# Lock-In.net
KiCad netlist of a schematic drawn in EAGLE
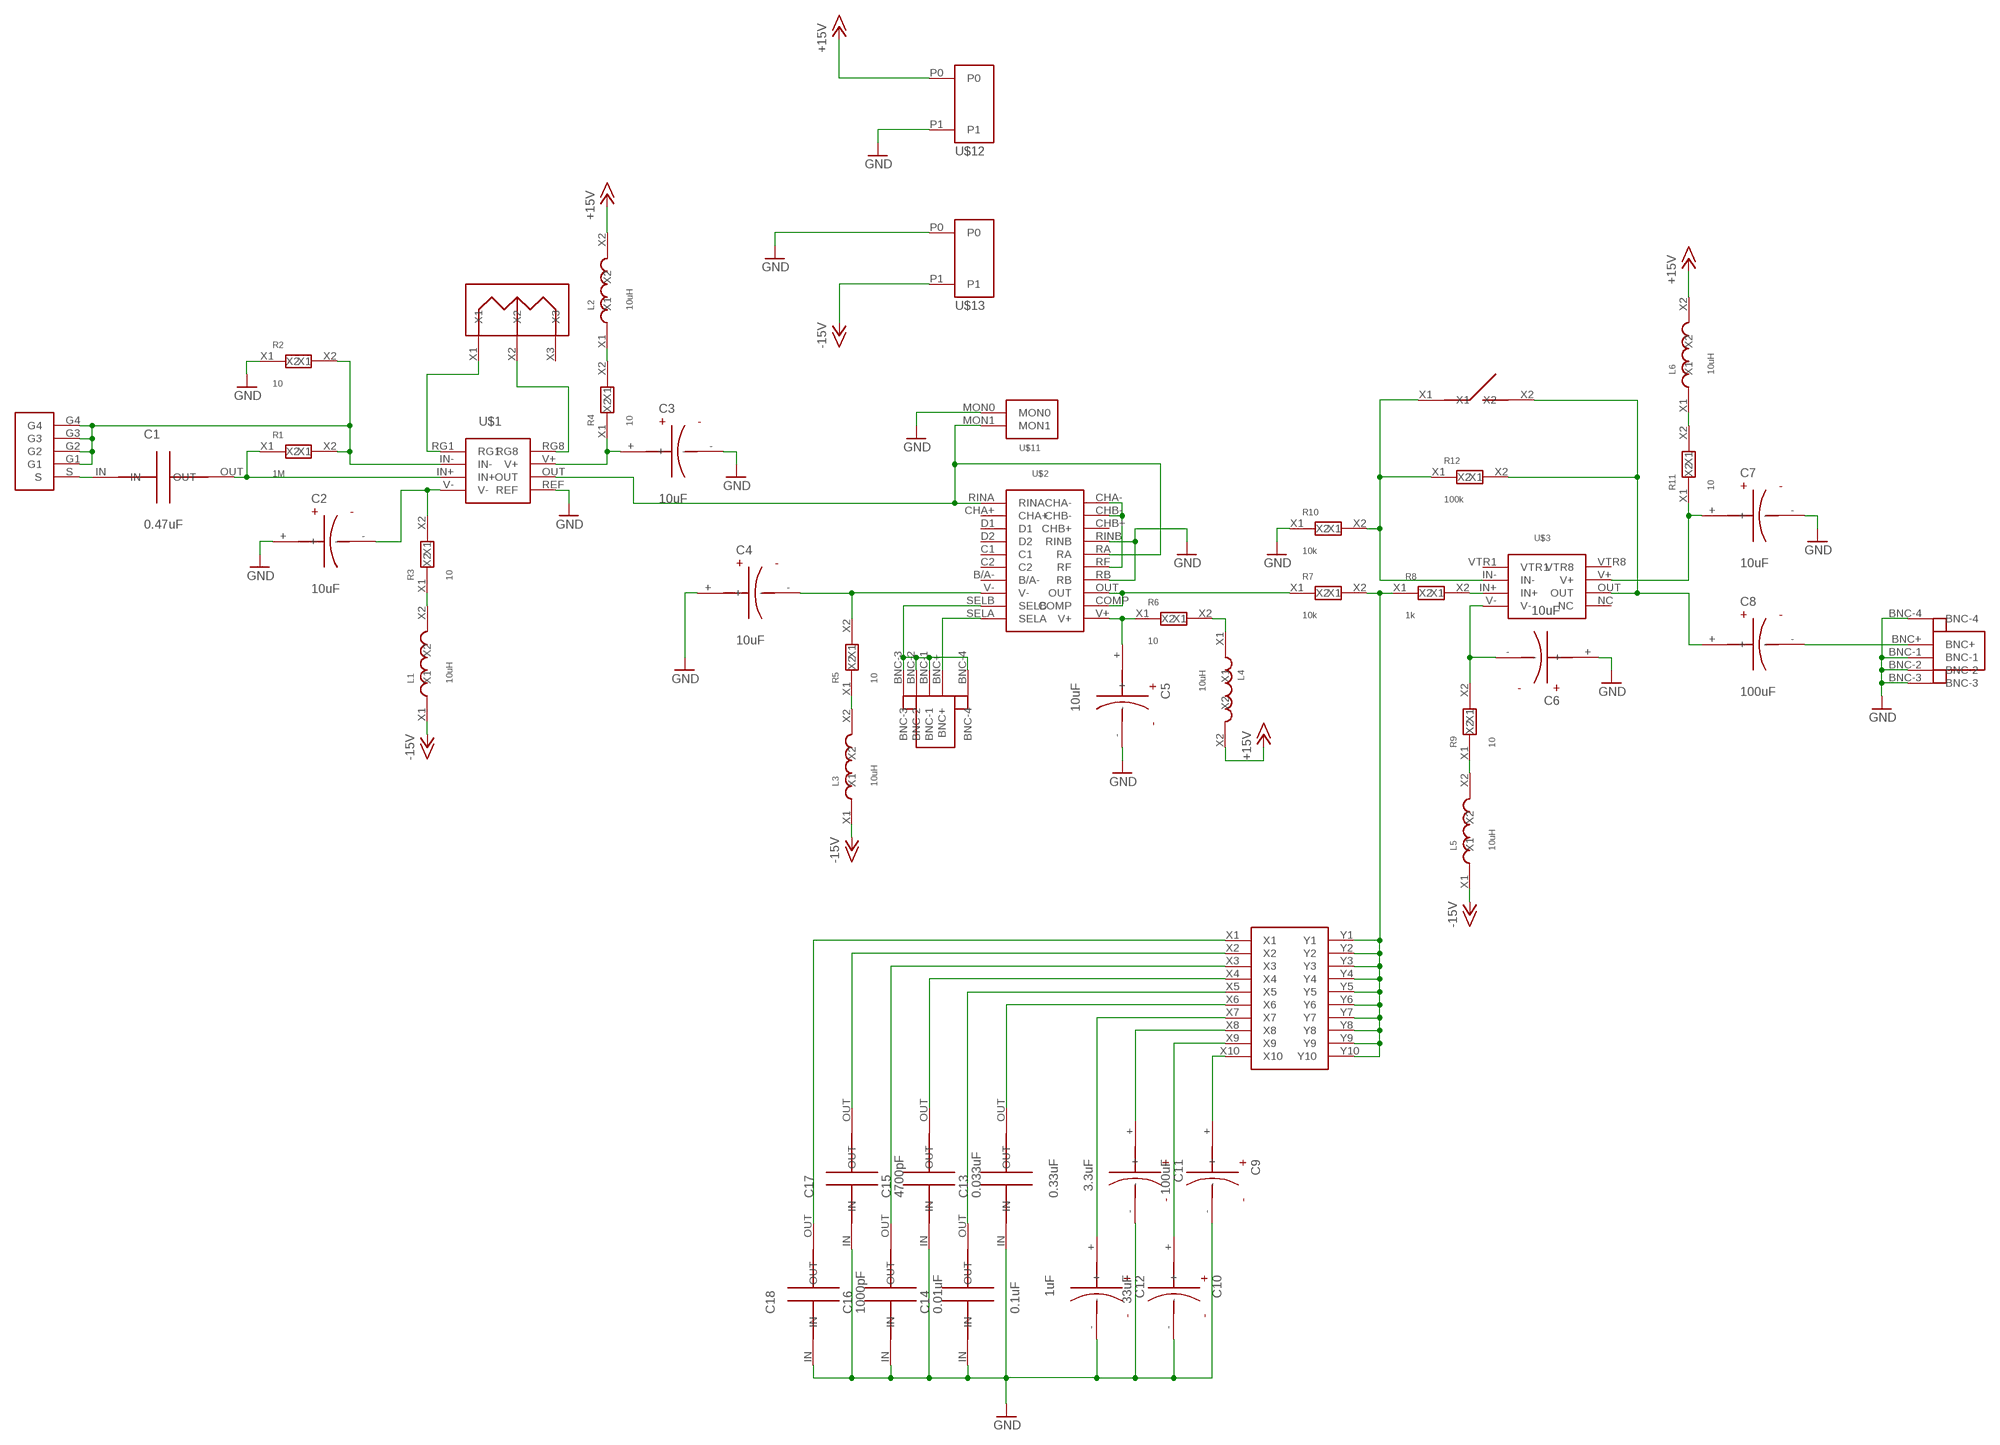
[diagram p0: schematic, sheet 1]

(export (version "E")
  (design (tool "Eeschema 10.0.6"))
  (components
    (comp (ref "C1")
      (value "0.47uF")
      (footprint "eagle-import:C_CER_5MM")
      (libsource (lib "eagle-import") (part "C_CER_5MM"))
    )
    (comp (ref "C2")
      (value "10uF")
      (footprint "eagle-import:C_ELT_2MM")
      (libsource (lib "eagle-import") (part "C_ELT_2MM"))
    )
    (comp (ref "C3")
      (value "10uF")
      (footprint "eagle-import:C_ELT_2MM")
      (libsource (lib "eagle-import") (part "C_ELT_2MM"))
    )
    (comp (ref "C4")
      (value "10uF")
      (footprint "eagle-import:C_ELT_2MM")
      (libsource (lib "eagle-import") (part "C_ELT_2MM"))
    )
    (comp (ref "C5")
      (value "10uF")
      (footprint "eagle-import:C_ELT_2MM")
      (libsource (lib "eagle-import") (part "C_ELT_2MM"))
    )
    (comp (ref "C6")
      (value "10uF")
      (footprint "eagle-import:C_ELT_2MM")
      (libsource (lib "eagle-import") (part "C_ELT_2MM"))
    )
    (comp (ref "C7")
      (value "10uF")
      (footprint "eagle-import:C_ELT_2MM")
      (libsource (lib "eagle-import") (part "C_ELT_2MM"))
    )
    (comp (ref "C8")
      (value "100uF")
      (footprint "eagle-import:C_ELT_2MM")
      (libsource (lib "eagle-import") (part "C_ELT_2MM"))
    )
    (comp (ref "C9")
      (value "100uF")
      (footprint "eagle-import:C_ELT_2MM")
      (libsource (lib "eagle-import") (part "C_ELT_2MM"))
    )
    (comp (ref "C10")
      (value "33uF")
      (footprint "eagle-import:C_ELT_2MM")
      (libsource (lib "eagle-import") (part "C_ELT_2MM"))
    )
    (comp (ref "C11")
      (value "3.3uF")
      (footprint "eagle-import:C_ELT_2MM")
      (libsource (lib "eagle-import") (part "C_ELT_2MM"))
    )
    (comp (ref "C12")
      (value "1uF")
      (footprint "eagle-import:C_ELT_2MM")
      (libsource (lib "eagle-import") (part "C_ELT_2MM"))
    )
    (comp (ref "C13")
      (value "0.33uF")
      (footprint "eagle-import:C_CER_5MM")
      (libsource (lib "eagle-import") (part "C_CER_5MM"))
    )
    (comp (ref "C14")
      (value "0.1uF")
      (footprint "eagle-import:C_CER_5MM")
      (libsource (lib "eagle-import") (part "C_CER_5MM"))
    )
    (comp (ref "C15")
      (value "0.033uF")
      (footprint "eagle-import:C_CER_5MM")
      (libsource (lib "eagle-import") (part "C_CER_5MM"))
    )
    (comp (ref "C16")
      (value "0.01uF")
      (footprint "eagle-import:C_CER_5MM")
      (libsource (lib "eagle-import") (part "C_CER_5MM"))
    )
    (comp (ref "C17")
      (value "4700pF")
      (footprint "eagle-import:C_CER_5MM")
      (libsource (lib "eagle-import") (part "C_CER_5MM"))
    )
    (comp (ref "C18")
      (value "1000pF")
      (footprint "eagle-import:C_CER_5MM")
      (libsource (lib "eagle-import") (part "C_CER_5MM"))
    )
    (comp (ref "L1")
      (value "10uH")
      (footprint "eagle-import:L_10X3")
      (libsource (lib "eagle-import") (part "L_10X3"))
    )
    (comp (ref "L2")
      (value "10uH")
      (footprint "eagle-import:L_10X3")
      (libsource (lib "eagle-import") (part "L_10X3"))
    )
    (comp (ref "L3")
      (value "10uH")
      (footprint "eagle-import:L_10X3")
      (libsource (lib "eagle-import") (part "L_10X3"))
    )
    (comp (ref "L4")
      (value "10uH")
      (footprint "eagle-import:L_10X3")
      (libsource (lib "eagle-import") (part "L_10X3"))
    )
    (comp (ref "L5")
      (value "10uH")
      (footprint "eagle-import:L_10X3")
      (libsource (lib "eagle-import") (part "L_10X3"))
    )
    (comp (ref "L6")
      (value "10uH")
      (footprint "eagle-import:L_10X3")
      (libsource (lib "eagle-import") (part "L_10X3"))
    )
    (comp (ref "R1")
      (value "1M")
      (footprint "eagle-import:R_6X2")
      (libsource (lib "eagle-import") (part "R_6X2"))
    )
    (comp (ref "R2")
      (value "10")
      (footprint "eagle-import:R_6X2")
      (libsource (lib "eagle-import") (part "R_6X2"))
    )
    (comp (ref "R3")
      (value "10")
      (footprint "eagle-import:R_6X2")
      (libsource (lib "eagle-import") (part "R_6X2"))
    )
    (comp (ref "R4")
      (value "10")
      (footprint "eagle-import:R_6X2")
      (libsource (lib "eagle-import") (part "R_6X2"))
    )
    (comp (ref "R5")
      (value "10")
      (footprint "eagle-import:R_6X2")
      (libsource (lib "eagle-import") (part "R_6X2"))
    )
    (comp (ref "R6")
      (value "10")
      (footprint "eagle-import:R_6X2")
      (libsource (lib "eagle-import") (part "R_6X2"))
    )
    (comp (ref "R7")
      (value "10k")
      (footprint "eagle-import:R_6X2")
      (libsource (lib "eagle-import") (part "R_6X2"))
    )
    (comp (ref "R8")
      (value "1k")
      (footprint "eagle-import:R_6X2")
      (libsource (lib "eagle-import") (part "R_6X2"))
    )
    (comp (ref "R9")
      (value "10")
      (footprint "eagle-import:R_6X2")
      (libsource (lib "eagle-import") (part "R_6X2"))
    )
    (comp (ref "R10")
      (value "10k")
      (footprint "eagle-import:R_6X2")
      (libsource (lib "eagle-import") (part "R_6X2"))
    )
    (comp (ref "R11")
      (value "10")
      (footprint "eagle-import:R_6X2")
      (libsource (lib "eagle-import") (part "R_6X2"))
    )
    (comp (ref "R12")
      (value "100k")
      (footprint "eagle-import:R_6X2")
      (libsource (lib "eagle-import") (part "R_6X2"))
    )
    (comp (ref "U$1")
      (value "AD620N")
      (footprint "eagle-import:AD620N")
      (libsource (lib "eagle-import") (part "AD620N"))
    )
    (comp (ref "U$2")
      (value "AD630")
      (footprint "eagle-import:AD630")
      (libsource (lib "eagle-import") (part "AD630"))
    )
    (comp (ref "U$3")
      (value "OP27")
      (footprint "eagle-import:OP27")
      (libsource (lib "eagle-import") (part "OP27"))
    )
    (comp (ref "U$4")
      (value "BNC")
      (footprint "eagle-import:BNC")
      (libsource (lib "eagle-import") (part "BNC"))
    )
    (comp (ref "U$5")
      (value "BNC")
      (footprint "eagle-import:BNC")
      (libsource (lib "eagle-import") (part "BNC"))
    )
    (comp (ref "U$6")
      (value "DIP10")
      (footprint "eagle-import:DIP10")
      (libsource (lib "eagle-import") (part "DIP10"))
    )
    (comp (ref "U$7")
      (value "R_VAR_10K")
      (footprint "eagle-import:R_VAR_10K")
      (libsource (lib "eagle-import") (part "R_VAR_10K"))
    )
    (comp (ref "U$8")
      (value "SMA_AN")
      (footprint "eagle-import:SMA_AN")
      (libsource (lib "eagle-import") (part "SMA_AN"))
    )
    (comp (ref "U$9")
      (value "DIP_1")
      (footprint "eagle-import:DIP_1")
      (libsource (lib "eagle-import") (part "DIP_1"))
    )
    (comp (ref "U$11")
      (value "MON2PIN")
      (footprint "eagle-import:MON2PIN")
      (libsource (lib "eagle-import") (part "MON2PIN"))
    )
    (comp (ref "U$12")
      (value "RAIL_2")
      (footprint "eagle-import:RAIL_2")
      (libsource (lib "eagle-import") (part "RAIL_2"))
    )
    (comp (ref "U$13")
      (value "RAIL_2")
      (footprint "eagle-import:RAIL_2")
      (libsource (lib "eagle-import") (part "RAIL_2"))
    )
  )
  (nets
    (net (code "1") (name "+15V") (class "Default")
      (node (ref "L2") (pin "X2") (pinfunction "X2_X2") (pintype "bidirectional"))
      (node (ref "L4") (pin "X2") (pinfunction "X2_X2") (pintype "bidirectional"))
      (node (ref "L6") (pin "X2") (pinfunction "X2_X2") (pintype "bidirectional"))
      (node (ref "U$12") (pin "P0") (pinfunction "P0_P0") (pintype "bidirectional"))
    )
    (net (code "2") (name "-15V") (class "Default")
      (node (ref "L1") (pin "X1") (pinfunction "X1_X1") (pintype "bidirectional"))
      (node (ref "L3") (pin "X1") (pinfunction "X1_X1") (pintype "bidirectional"))
      (node (ref "L5") (pin "X1") (pinfunction "X1_X1") (pintype "bidirectional"))
      (node (ref "U$13") (pin "P1") (pinfunction "P1_P1") (pintype "bidirectional"))
    )
    (net (code "3") (name "GND") (class "Default")
      (node (ref "C10") (pin "-") (pinfunction "-_-") (pintype "bidirectional"))
      (node (ref "C11") (pin "-") (pinfunction "-_-") (pintype "bidirectional"))
      (node (ref "C12") (pin "-") (pinfunction "-_-") (pintype "bidirectional"))
      (node (ref "C13") (pin "IN") (pinfunction "IN_IN") (pintype "bidirectional"))
      (node (ref "C14") (pin "IN") (pinfunction "IN_IN") (pintype "bidirectional"))
      (node (ref "C15") (pin "IN") (pinfunction "IN_IN") (pintype "bidirectional"))
      (node (ref "C16") (pin "IN") (pinfunction "IN_IN") (pintype "bidirectional"))
      (node (ref "C17") (pin "IN") (pinfunction "IN_IN") (pintype "bidirectional"))
      (node (ref "C18") (pin "IN") (pinfunction "IN_IN") (pintype "bidirectional"))
      (node (ref "C2") (pin "+") (pinfunction "+_+") (pintype "bidirectional"))
      (node (ref "C3") (pin "-") (pinfunction "-_-") (pintype "bidirectional"))
      (node (ref "C4") (pin "+") (pinfunction "+_+") (pintype "bidirectional"))
      (node (ref "C5") (pin "-") (pinfunction "-_-") (pintype "bidirectional"))
      (node (ref "C6") (pin "+") (pinfunction "+_+") (pintype "bidirectional"))
      (node (ref "C7") (pin "-") (pinfunction "-_-") (pintype "bidirectional"))
      (node (ref "C9") (pin "-") (pinfunction "-_-") (pintype "bidirectional"))
      (node (ref "R10") (pin "X1") (pinfunction "X1_X1") (pintype "bidirectional"))
      (node (ref "R2") (pin "X1") (pinfunction "X1_X1") (pintype "bidirectional"))
      (node (ref "U$1") (pin "REF") (pinfunction "REF_REF") (pintype "bidirectional"))
      (node (ref "U$11") (pin "MON0") (pinfunction "MON0_MON0") (pintype "bidirectional"))
      (node (ref "U$12") (pin "P1") (pinfunction "P1_P1") (pintype "bidirectional"))
      (node (ref "U$13") (pin "P0") (pinfunction "P0_P0") (pintype "bidirectional"))
      (node (ref "U$2") (pin "RB") (pinfunction "RB_RB") (pintype "bidirectional"))
      (node (ref "U$2") (pin "RINB") (pinfunction "RINB_RINB") (pintype "bidirectional"))
      (node (ref "U$5") (pin "BNC-1") (pinfunction "BNC-1_BNC-1") (pintype "bidirectional"))
      (node (ref "U$5") (pin "BNC-2") (pinfunction "BNC-2_BNC-2") (pintype "bidirectional"))
      (node (ref "U$5") (pin "BNC-3") (pinfunction "BNC-3_BNC-3") (pintype "bidirectional"))
      (node (ref "U$5") (pin "BNC-4") (pinfunction "BNC-4_BNC-4") (pintype "bidirectional"))
    )
    (net (code "4") (name "Net-(C1-PadIN)") (class "Default")
      (node (ref "C1") (pin "IN") (pinfunction "IN_IN") (pintype "bidirectional"))
      (node (ref "U$8") (pin "S") (pinfunction "S_S") (pintype "bidirectional"))
    )
    (net (code "5") (name "Net-(C1-PadOUT)") (class "Default")
      (node (ref "C1") (pin "OUT") (pinfunction "OUT_OUT") (pintype "bidirectional"))
      (node (ref "R1") (pin "X1") (pinfunction "X1_X1") (pintype "bidirectional"))
      (node (ref "U$1") (pin "IN+") (pinfunction "IN+_IN+") (pintype "bidirectional"))
    )
    (net (code "6") (name "Net-(C2-Pad-)") (class "Default")
      (node (ref "C2") (pin "-") (pinfunction "-_-") (pintype "bidirectional"))
      (node (ref "R3") (pin "X2") (pinfunction "X2_X2") (pintype "bidirectional"))
      (node (ref "U$1") (pin "V-") (pinfunction "V-_V-") (pintype "bidirectional"))
    )
    (net (code "7") (name "Net-(C3-Pad+)") (class "Default")
      (node (ref "C3") (pin "+") (pinfunction "+_+") (pintype "bidirectional"))
      (node (ref "R4") (pin "X1") (pinfunction "X1_X1") (pintype "bidirectional"))
      (node (ref "U$1") (pin "V+") (pinfunction "V+_V+") (pintype "bidirectional"))
    )
    (net (code "8") (name "Net-(C4-Pad-)") (class "Default")
      (node (ref "C4") (pin "-") (pinfunction "-_-") (pintype "bidirectional"))
      (node (ref "R5") (pin "X2") (pinfunction "X2_X2") (pintype "bidirectional"))
      (node (ref "U$2") (pin "V-") (pinfunction "V-_V-") (pintype "bidirectional"))
    )
    (net (code "9") (name "Net-(C5-Pad+)") (class "Default")
      (node (ref "C5") (pin "+") (pinfunction "+_+") (pintype "bidirectional"))
      (node (ref "R6") (pin "X1") (pinfunction "X1_X1") (pintype "bidirectional"))
      (node (ref "U$2") (pin "V+") (pinfunction "V+_V+") (pintype "bidirectional"))
    )
    (net (code "10") (name "Net-(C6-Pad-)") (class "Default")
      (node (ref "C6") (pin "-") (pinfunction "-_-") (pintype "bidirectional"))
      (node (ref "R9") (pin "X2") (pinfunction "X2_X2") (pintype "bidirectional"))
      (node (ref "U$3") (pin "V-") (pinfunction "V-_V-") (pintype "bidirectional"))
    )
    (net (code "11") (name "Net-(C7-Pad+)") (class "Default")
      (node (ref "C7") (pin "+") (pinfunction "+_+") (pintype "bidirectional"))
      (node (ref "R11") (pin "X1") (pinfunction "X1_X1") (pintype "bidirectional"))
      (node (ref "U$3") (pin "V+") (pinfunction "V+_V+") (pintype "bidirectional"))
    )
    (net (code "12") (name "Net-(C8-Pad+)") (class "Default")
      (node (ref "C8") (pin "+") (pinfunction "+_+") (pintype "bidirectional"))
      (node (ref "R12") (pin "X2") (pinfunction "X2_X2") (pintype "bidirectional"))
      (node (ref "U$3") (pin "OUT") (pinfunction "OUT_OUT") (pintype "bidirectional"))
      (node (ref "U$9") (pin "X2") (pinfunction "X2_X2") (pintype "bidirectional"))
    )
    (net (code "13") (name "Net-(C8-Pad-)") (class "Default")
      (node (ref "C8") (pin "-") (pinfunction "-_-") (pintype "bidirectional"))
      (node (ref "U$5") (pin "BNC+") (pinfunction "BNC+_BNC+") (pintype "bidirectional"))
    )
    (net (code "14") (name "Net-(C9-Pad+)") (class "Default")
      (node (ref "C9") (pin "+") (pinfunction "+_+") (pintype "bidirectional"))
      (node (ref "U$6") (pin "X10") (pinfunction "X10_X10") (pintype "bidirectional"))
    )
    (net (code "15") (name "Net-(C10-Pad+)") (class "Default")
      (node (ref "C10") (pin "+") (pinfunction "+_+") (pintype "bidirectional"))
      (node (ref "U$6") (pin "X9") (pinfunction "X9_X9") (pintype "bidirectional"))
    )
    (net (code "16") (name "Net-(C11-Pad+)") (class "Default")
      (node (ref "C11") (pin "+") (pinfunction "+_+") (pintype "bidirectional"))
      (node (ref "U$6") (pin "X8") (pinfunction "X8_X8") (pintype "bidirectional"))
    )
    (net (code "17") (name "Net-(C12-Pad+)") (class "Default")
      (node (ref "C12") (pin "+") (pinfunction "+_+") (pintype "bidirectional"))
      (node (ref "U$6") (pin "X7") (pinfunction "X7_X7") (pintype "bidirectional"))
    )
    (net (code "18") (name "Net-(C13-PadOUT)") (class "Default")
      (node (ref "C13") (pin "OUT") (pinfunction "OUT_OUT") (pintype "bidirectional"))
      (node (ref "U$6") (pin "X6") (pinfunction "X6_X6") (pintype "bidirectional"))
    )
    (net (code "19") (name "Net-(C14-PadOUT)") (class "Default")
      (node (ref "C14") (pin "OUT") (pinfunction "OUT_OUT") (pintype "bidirectional"))
      (node (ref "U$6") (pin "X5") (pinfunction "X5_X5") (pintype "bidirectional"))
    )
    (net (code "20") (name "Net-(C15-PadOUT)") (class "Default")
      (node (ref "C15") (pin "OUT") (pinfunction "OUT_OUT") (pintype "bidirectional"))
      (node (ref "U$6") (pin "X4") (pinfunction "X4_X4") (pintype "bidirectional"))
    )
    (net (code "21") (name "Net-(C16-PadOUT)") (class "Default")
      (node (ref "C16") (pin "OUT") (pinfunction "OUT_OUT") (pintype "bidirectional"))
      (node (ref "U$6") (pin "X3") (pinfunction "X3_X3") (pintype "bidirectional"))
    )
    (net (code "22") (name "Net-(C17-PadOUT)") (class "Default")
      (node (ref "C17") (pin "OUT") (pinfunction "OUT_OUT") (pintype "bidirectional"))
      (node (ref "U$6") (pin "X2") (pinfunction "X2_X2") (pintype "bidirectional"))
    )
    (net (code "23") (name "Net-(C18-PadOUT)") (class "Default")
      (node (ref "C18") (pin "OUT") (pinfunction "OUT_OUT") (pintype "bidirectional"))
      (node (ref "U$6") (pin "X1") (pinfunction "X1_X1") (pintype "bidirectional"))
    )
    (net (code "24") (name "Net-(L1-PadX2)") (class "Default")
      (node (ref "L1") (pin "X2") (pinfunction "X2_X2") (pintype "bidirectional"))
      (node (ref "R3") (pin "X1") (pinfunction "X1_X1") (pintype "bidirectional"))
    )
    (net (code "25") (name "Net-(L2-PadX1)") (class "Default")
      (node (ref "L2") (pin "X1") (pinfunction "X1_X1") (pintype "bidirectional"))
      (node (ref "R4") (pin "X2") (pinfunction "X2_X2") (pintype "bidirectional"))
    )
    (net (code "26") (name "Net-(L3-PadX2)") (class "Default")
      (node (ref "L3") (pin "X2") (pinfunction "X2_X2") (pintype "bidirectional"))
      (node (ref "R5") (pin "X1") (pinfunction "X1_X1") (pintype "bidirectional"))
    )
    (net (code "27") (name "Net-(L4-PadX1)") (class "Default")
      (node (ref "L4") (pin "X1") (pinfunction "X1_X1") (pintype "bidirectional"))
      (node (ref "R6") (pin "X2") (pinfunction "X2_X2") (pintype "bidirectional"))
    )
    (net (code "28") (name "Net-(L5-PadX2)") (class "Default")
      (node (ref "L5") (pin "X2") (pinfunction "X2_X2") (pintype "bidirectional"))
      (node (ref "R9") (pin "X1") (pinfunction "X1_X1") (pintype "bidirectional"))
    )
    (net (code "29") (name "Net-(L6-PadX1)") (class "Default")
      (node (ref "L6") (pin "X1") (pinfunction "X1_X1") (pintype "bidirectional"))
      (node (ref "R11") (pin "X2") (pinfunction "X2_X2") (pintype "bidirectional"))
    )
    (net (code "30") (name "Net-(R1-PadX2)") (class "Default")
      (node (ref "R1") (pin "X2") (pinfunction "X2_X2") (pintype "bidirectional"))
      (node (ref "R2") (pin "X2") (pinfunction "X2_X2") (pintype "bidirectional"))
      (node (ref "U$1") (pin "IN-") (pinfunction "IN-_IN-") (pintype "bidirectional"))
      (node (ref "U$8") (pin "G1") (pinfunction "G1_G1") (pintype "bidirectional"))
      (node (ref "U$8") (pin "G2") (pinfunction "G2_G2") (pintype "bidirectional"))
      (node (ref "U$8") (pin "G3") (pinfunction "G3_G3") (pintype "bidirectional"))
      (node (ref "U$8") (pin "G4") (pinfunction "G4_G4") (pintype "bidirectional"))
    )
    (net (code "31") (name "Net-(R7-PadX1)") (class "Default")
      (node (ref "R7") (pin "X1") (pinfunction "X1_X1") (pintype "bidirectional"))
      (node (ref "U$2") (pin "COMP") (pinfunction "COMP_COMP") (pintype "bidirectional"))
      (node (ref "U$2") (pin "OUT") (pinfunction "OUT_OUT") (pintype "bidirectional"))
    )
    (net (code "32") (name "Net-(R7-PadX2)") (class "Default")
      (node (ref "R7") (pin "X2") (pinfunction "X2_X2") (pintype "bidirectional"))
      (node (ref "R8") (pin "X1") (pinfunction "X1_X1") (pintype "bidirectional"))
      (node (ref "U$6") (pin "Y1") (pinfunction "Y1_Y1") (pintype "bidirectional"))
      (node (ref "U$6") (pin "Y10") (pinfunction "Y10_Y10") (pintype "bidirectional"))
      (node (ref "U$6") (pin "Y2") (pinfunction "Y2_Y2") (pintype "bidirectional"))
      (node (ref "U$6") (pin "Y3") (pinfunction "Y3_Y3") (pintype "bidirectional"))
      (node (ref "U$6") (pin "Y4") (pinfunction "Y4_Y4") (pintype "bidirectional"))
      (node (ref "U$6") (pin "Y5") (pinfunction "Y5_Y5") (pintype "bidirectional"))
      (node (ref "U$6") (pin "Y6") (pinfunction "Y6_Y6") (pintype "bidirectional"))
      (node (ref "U$6") (pin "Y7") (pinfunction "Y7_Y7") (pintype "bidirectional"))
      (node (ref "U$6") (pin "Y8") (pinfunction "Y8_Y8") (pintype "bidirectional"))
      (node (ref "U$6") (pin "Y9") (pinfunction "Y9_Y9") (pintype "bidirectional"))
    )
    (net (code "33") (name "Net-(R8-PadX2)") (class "Default")
      (node (ref "R8") (pin "X2") (pinfunction "X2_X2") (pintype "bidirectional"))
      (node (ref "U$3") (pin "IN+") (pinfunction "IN+_IN+") (pintype "bidirectional"))
    )
    (net (code "34") (name "Net-(R10-PadX2)") (class "Default")
      (node (ref "R10") (pin "X2") (pinfunction "X2_X2") (pintype "bidirectional"))
      (node (ref "R12") (pin "X1") (pinfunction "X1_X1") (pintype "bidirectional"))
      (node (ref "U$3") (pin "IN-") (pinfunction "IN-_IN-") (pintype "bidirectional"))
      (node (ref "U$9") (pin "X1") (pinfunction "X1_X1") (pintype "bidirectional"))
    )
    (net (code "35") (name "Net-(U$1-PadOUT)") (class "Default")
      (node (ref "U$1") (pin "OUT") (pinfunction "OUT_OUT") (pintype "bidirectional"))
      (node (ref "U$11") (pin "MON1") (pinfunction "MON1_MON1") (pintype "bidirectional"))
      (node (ref "U$2") (pin "RA") (pinfunction "RA_RA") (pintype "bidirectional"))
      (node (ref "U$2") (pin "RINA") (pinfunction "RINA_RINA") (pintype "bidirectional"))
    )
    (net (code "36") (name "Net-(U$1-PadRG1)") (class "Default")
      (node (ref "U$1") (pin "RG1") (pinfunction "RG1_RG1") (pintype "bidirectional"))
      (node (ref "U$7") (pin "X1") (pinfunction "X1_X1") (pintype "bidirectional"))
    )
    (net (code "37") (name "Net-(U$1-PadRG8)") (class "Default")
      (node (ref "U$1") (pin "RG8") (pinfunction "RG8_RG8") (pintype "bidirectional"))
      (node (ref "U$7") (pin "X2") (pinfunction "X2_X2") (pintype "bidirectional"))
    )
    (net (code "38") (name "Net-(U$2-PadCHA-)") (class "Default")
      (node (ref "U$2") (pin "CHA-") (pinfunction "CHA-_CHA-") (pintype "bidirectional"))
      (node (ref "U$2") (pin "CHB-") (pinfunction "CHB-_CHB-") (pintype "bidirectional"))
      (node (ref "U$2") (pin "RF") (pinfunction "RF_RF") (pintype "bidirectional"))
    )
    (net (code "39") (name "Net-(U$2-PadSELA)") (class "Default")
      (node (ref "U$2") (pin "SELA") (pinfunction "SELA_SELA") (pintype "bidirectional"))
      (node (ref "U$4") (pin "BNC+") (pinfunction "BNC+_BNC+") (pintype "bidirectional"))
    )
    (net (code "40") (name "Net-(U$2-PadSELB)") (class "Default")
      (node (ref "U$2") (pin "SELB") (pinfunction "SELB_SELB") (pintype "bidirectional"))
      (node (ref "U$4") (pin "BNC-1") (pinfunction "BNC-1_BNC-1") (pintype "bidirectional"))
      (node (ref "U$4") (pin "BNC-2") (pinfunction "BNC-2_BNC-2") (pintype "bidirectional"))
      (node (ref "U$4") (pin "BNC-3") (pinfunction "BNC-3_BNC-3") (pintype "bidirectional"))
      (node (ref "U$4") (pin "BNC-4") (pinfunction "BNC-4_BNC-4") (pintype "bidirectional"))
    )
    (net (code "41") (name "unconnected-(U$2-PadB{slash}A-)") (class "Default")
      (node (ref "U$2") (pin "B/A-") (pinfunction "B/A-_B/A-") (pintype "bidirectional"))
    )
    (net (code "42") (name "unconnected-(U$2-PadC1)") (class "Default")
      (node (ref "U$2") (pin "C1") (pinfunction "C1_C1") (pintype "bidirectional"))
    )
    (net (code "43") (name "unconnected-(U$2-PadC2)") (class "Default")
      (node (ref "U$2") (pin "C2") (pinfunction "C2_C2") (pintype "bidirectional"))
    )
    (net (code "44") (name "unconnected-(U$2-PadCHA+)") (class "Default")
      (node (ref "U$2") (pin "CHA+") (pinfunction "CHA+_CHA+") (pintype "bidirectional"))
    )
    (net (code "45") (name "unconnected-(U$2-PadCHB+)") (class "Default")
      (node (ref "U$2") (pin "CHB+") (pinfunction "CHB+_CHB+") (pintype "bidirectional"))
    )
    (net (code "46") (name "unconnected-(U$2-PadD1)") (class "Default")
      (node (ref "U$2") (pin "D1") (pinfunction "D1_D1") (pintype "bidirectional"))
    )
    (net (code "47") (name "unconnected-(U$2-PadD2)") (class "Default")
      (node (ref "U$2") (pin "D2") (pinfunction "D2_D2") (pintype "bidirectional"))
    )
    (net (code "48") (name "unconnected-(U$3-PadNC)") (class "Default")
      (node (ref "U$3") (pin "NC") (pinfunction "NC_NC") (pintype "bidirectional"))
    )
    (net (code "49") (name "unconnected-(U$3-PadVTR1)") (class "Default")
      (node (ref "U$3") (pin "VTR1") (pinfunction "VTR1_VTR1") (pintype "bidirectional"))
    )
    (net (code "50") (name "unconnected-(U$3-PadVTR8)") (class "Default")
      (node (ref "U$3") (pin "VTR8") (pinfunction "VTR8_VTR8") (pintype "bidirectional"))
    )
    (net (code "51") (name "unconnected-(U$7-PadX3)") (class "Default")
      (node (ref "U$7") (pin "X3") (pinfunction "X3_X3") (pintype "bidirectional"))
    )
  )
)
